# breezeduino.net
KiCad netlist of a schematic drawn in EAGLE
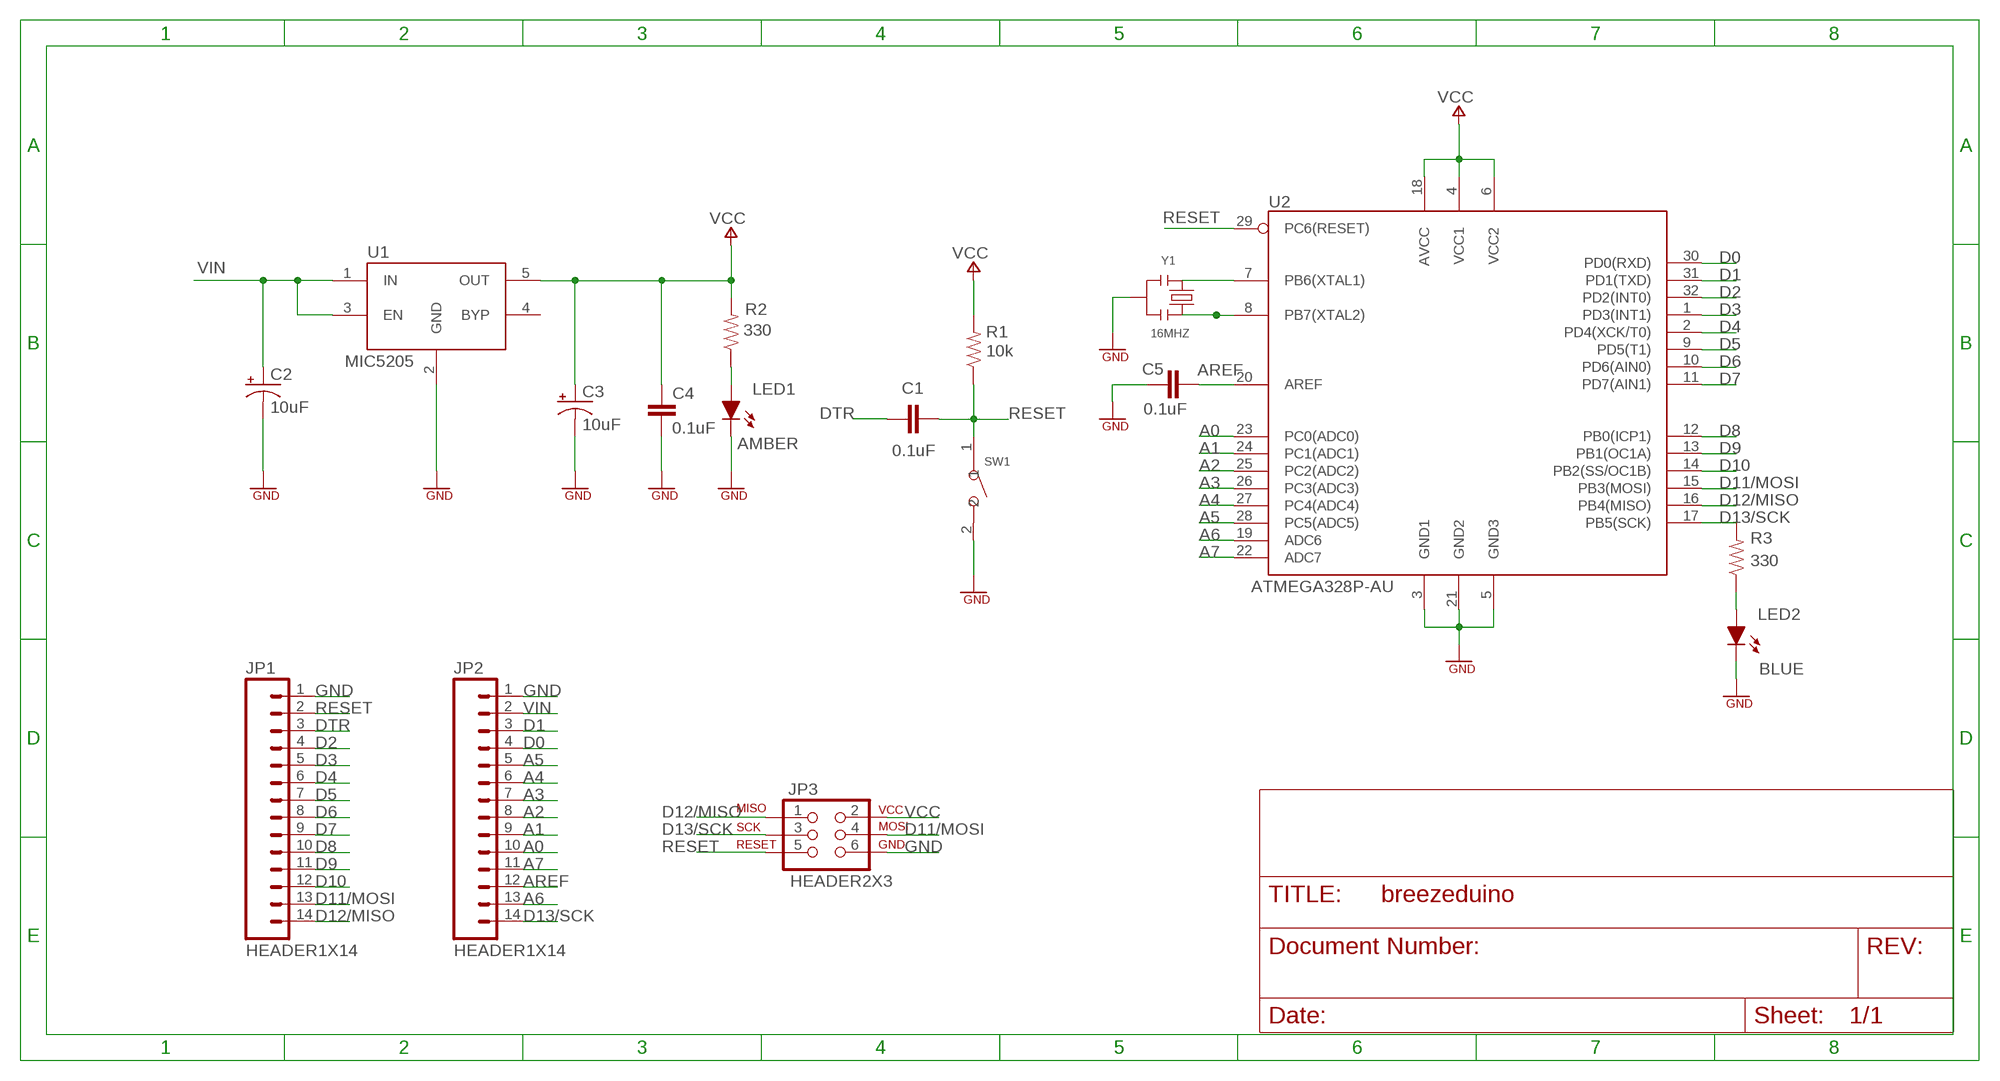
[diagram p0: schematic, sheet 1]

(export (version "E")
  (design (tool "Eeschema 10.0.6"))
  (components
    (comp (ref "C1")
      (value "0.1uF")
      (footprint "eagle-import:SMD0603")
      (libsource (lib "eagle-import") (part "CAP_0603"))
    )
    (comp (ref "C2")
      (value "10uF")
      (footprint "eagle-import:EIA3216")
      (libsource (lib "eagle-import") (part "CAP_TANT"))
    )
    (comp (ref "C3")
      (value "10uF")
      (footprint "eagle-import:EIA3216")
      (libsource (lib "eagle-import") (part "CAP_TANT"))
    )
    (comp (ref "C4")
      (value "0.1uF")
      (footprint "eagle-import:SMD0603")
      (libsource (lib "eagle-import") (part "CAP_0603"))
    )
    (comp (ref "C5")
      (value "0.1uF")
      (footprint "eagle-import:SMD0603")
      (libsource (lib "eagle-import") (part "CAP_0603"))
    )
    (comp (ref "JP1")
      (value "HEADER1X14")
      (footprint "eagle-import:1X14")
      (libsource (lib "eagle-import") (part "HEADER1X14"))
    )
    (comp (ref "JP2")
      (value "HEADER1X14")
      (footprint "eagle-import:1X14")
      (libsource (lib "eagle-import") (part "HEADER1X14"))
    )
    (comp (ref "JP3")
      (value "HEADER2X3")
      (footprint "eagle-import:2X3")
      (libsource (lib "eagle-import") (part "HEADER2X3"))
    )
    (comp (ref "LED1")
      (value "AMBER")
      (footprint "eagle-import:LED_0603")
      (libsource (lib "eagle-import") (part "LED_0603"))
    )
    (comp (ref "LED2")
      (value "BLUE")
      (footprint "eagle-import:LED_0805")
      (libsource (lib "eagle-import") (part "LED_0805"))
    )
    (comp (ref "R1")
      (value "10k")
      (footprint "eagle-import:SMD0603")
      (libsource (lib "eagle-import") (part "RES_0603"))
    )
    (comp (ref "R2")
      (value "330")
      (footprint "eagle-import:SMD0603")
      (libsource (lib "eagle-import") (part "RES_0603"))
    )
    (comp (ref "R3")
      (value "330")
      (footprint "eagle-import:SMD0603")
      (libsource (lib "eagle-import") (part "RES_0603"))
    )
    (comp (ref "SW1")
      (value "SMD-BUTTON(2P-3.0X2.5X1.2+0.4MM)-B3U-1000P-2P-SMD")
      (footprint "eagle-import:SW2-2.6-3.0X2.5X1.2+0.4MM")
      (fields (field (name "MPN") "B3U-1000P-2P-SMD"))
      (libsource (lib "eagle-import") (part "SMD-BUTTON(2P-3.0X2.5X1.2+0.4MM)-B3U-1000P-2P-SMD"))
    )
    (comp (ref "U1")
      (value "MIC5205")
      (footprint "eagle-import:SOT23-5")
      (libsource (lib "eagle-import") (part "MIC5205"))
    )
    (comp (ref "U2")
      (value "ATMEGA328P-AU")
      (footprint "eagle-import:TQFP32")
      (libsource (lib "eagle-import") (part "ATMEGA328P-AU"))
    )
    (comp (ref "Y1")
      (value "16MHZ")
      (footprint "eagle-import:X3-SMD-3.6X1.3X0.8MM")
      (fields (field (name "MPN") "CSTCE16M0V53-R0"))
      (libsource (lib "eagle-import") (part "SMD-RESONATOR-16MHZ-15PF-0.5%-40R(3P-3.2X1.3MM)"))
    )
  )
  (nets
    (net (code "1") (name "/A0") (class "Default")
      (node (ref "JP2") (pin "10") (pinfunction "10_10") (pintype "passive"))
      (node (ref "U2") (pin "23") (pinfunction "PC0(ADC0)_23") (pintype "bidirectional"))
    )
    (net (code "2") (name "/A1") (class "Default")
      (node (ref "JP2") (pin "9") (pinfunction "9_9") (pintype "passive"))
      (node (ref "U2") (pin "24") (pinfunction "PC1(ADC1)_24") (pintype "bidirectional"))
    )
    (net (code "3") (name "/A2") (class "Default")
      (node (ref "JP2") (pin "8") (pinfunction "8_8") (pintype "passive"))
      (node (ref "U2") (pin "25") (pinfunction "PC2(ADC2)_25") (pintype "bidirectional"))
    )
    (net (code "4") (name "/A3") (class "Default")
      (node (ref "JP2") (pin "7") (pinfunction "7_7") (pintype "passive"))
      (node (ref "U2") (pin "26") (pinfunction "PC3(ADC3)_26") (pintype "bidirectional"))
    )
    (net (code "5") (name "/A4") (class "Default")
      (node (ref "JP2") (pin "6") (pinfunction "6_6") (pintype "passive"))
      (node (ref "U2") (pin "27") (pinfunction "PC4(ADC4)_27") (pintype "bidirectional"))
    )
    (net (code "6") (name "/A5") (class "Default")
      (node (ref "JP2") (pin "5") (pinfunction "5_5") (pintype "passive"))
      (node (ref "U2") (pin "28") (pinfunction "PC5(ADC5)_28") (pintype "bidirectional"))
    )
    (net (code "7") (name "/A6") (class "Default")
      (node (ref "JP2") (pin "13") (pinfunction "13_13") (pintype "passive"))
      (node (ref "U2") (pin "19") (pinfunction "ADC6_19") (pintype "bidirectional"))
    )
    (net (code "8") (name "/A7") (class "Default")
      (node (ref "JP2") (pin "11") (pinfunction "11_11") (pintype "passive"))
      (node (ref "U2") (pin "22") (pinfunction "ADC7_22") (pintype "bidirectional"))
    )
    (net (code "9") (name "/AREF") (class "Default")
      (node (ref "C5") (pin "1") (pinfunction "1_1") (pintype "passive"))
      (node (ref "JP2") (pin "12") (pinfunction "12_12") (pintype "passive"))
      (node (ref "U2") (pin "20") (pinfunction "AREF_20") (pintype "bidirectional"))
    )
    (net (code "10") (name "/D0") (class "Default")
      (node (ref "JP2") (pin "4") (pinfunction "4_4") (pintype "passive"))
      (node (ref "U2") (pin "30") (pinfunction "PD0(RXD)_30") (pintype "bidirectional"))
    )
    (net (code "11") (name "/D1") (class "Default")
      (node (ref "JP2") (pin "3") (pinfunction "3_3") (pintype "passive"))
      (node (ref "U2") (pin "31") (pinfunction "PD1(TXD)_31") (pintype "bidirectional"))
    )
    (net (code "12") (name "/D2") (class "Default")
      (node (ref "JP1") (pin "4") (pinfunction "4_4") (pintype "passive"))
      (node (ref "U2") (pin "32") (pinfunction "PD2(INT0)_32") (pintype "bidirectional"))
    )
    (net (code "13") (name "/D3") (class "Default")
      (node (ref "JP1") (pin "5") (pinfunction "5_5") (pintype "passive"))
      (node (ref "U2") (pin "1") (pinfunction "PD3(INT1)_1") (pintype "bidirectional"))
    )
    (net (code "14") (name "/D4") (class "Default")
      (node (ref "JP1") (pin "6") (pinfunction "6_6") (pintype "passive"))
      (node (ref "U2") (pin "2") (pinfunction "PD4(XCK/T0)_2") (pintype "bidirectional"))
    )
    (net (code "15") (name "/D5") (class "Default")
      (node (ref "JP1") (pin "7") (pinfunction "7_7") (pintype "passive"))
      (node (ref "U2") (pin "9") (pinfunction "PD5(T1)_9") (pintype "bidirectional"))
    )
    (net (code "16") (name "/D6") (class "Default")
      (node (ref "JP1") (pin "8") (pinfunction "8_8") (pintype "passive"))
      (node (ref "U2") (pin "10") (pinfunction "PD6(AIN0)_10") (pintype "bidirectional"))
    )
    (net (code "17") (name "/D7") (class "Default")
      (node (ref "JP1") (pin "9") (pinfunction "9_9") (pintype "passive"))
      (node (ref "U2") (pin "11") (pinfunction "PD7(AIN1)_11") (pintype "bidirectional"))
    )
    (net (code "18") (name "/D8") (class "Default")
      (node (ref "JP1") (pin "10") (pinfunction "10_10") (pintype "passive"))
      (node (ref "U2") (pin "12") (pinfunction "PB0(ICP1)_12") (pintype "bidirectional"))
    )
    (net (code "19") (name "/D9") (class "Default")
      (node (ref "JP1") (pin "11") (pinfunction "11_11") (pintype "passive"))
      (node (ref "U2") (pin "13") (pinfunction "PB1(OC1A)_13") (pintype "bidirectional"))
    )
    (net (code "20") (name "/D10") (class "Default")
      (node (ref "JP1") (pin "12") (pinfunction "12_12") (pintype "passive"))
      (node (ref "U2") (pin "14") (pinfunction "PB2(SS/OC1B)_14") (pintype "bidirectional"))
    )
    (net (code "21") (name "/D11{slash}MOSI") (class "Default")
      (node (ref "JP1") (pin "13") (pinfunction "13_13") (pintype "passive"))
      (node (ref "JP3") (pin "4") (pinfunction "4_4") (pintype "passive"))
      (node (ref "U2") (pin "15") (pinfunction "PB3(MOSI)_15") (pintype "bidirectional"))
    )
    (net (code "22") (name "/D12{slash}MISO") (class "Default")
      (node (ref "JP1") (pin "14") (pinfunction "14_14") (pintype "passive"))
      (node (ref "JP3") (pin "1") (pinfunction "1_1") (pintype "passive"))
      (node (ref "U2") (pin "16") (pinfunction "PB4(MISO)_16") (pintype "bidirectional"))
    )
    (net (code "23") (name "/D13{slash}SCK") (class "Default")
      (node (ref "JP2") (pin "14") (pinfunction "14_14") (pintype "passive"))
      (node (ref "JP3") (pin "3") (pinfunction "3_3") (pintype "passive"))
      (node (ref "R3") (pin "2") (pinfunction "2_2") (pintype "passive"))
      (node (ref "U2") (pin "17") (pinfunction "PB5(SCK)_17") (pintype "bidirectional"))
    )
    (net (code "24") (name "/DTR") (class "Default")
      (node (ref "C1") (pin "1") (pinfunction "1_1") (pintype "passive"))
      (node (ref "JP1") (pin "3") (pinfunction "3_3") (pintype "passive"))
    )
    (net (code "25") (name "/RESET") (class "Default")
      (node (ref "C1") (pin "2") (pinfunction "2_2") (pintype "passive"))
      (node (ref "JP1") (pin "2") (pinfunction "2_2") (pintype "passive"))
      (node (ref "JP3") (pin "5") (pinfunction "5_5") (pintype "passive"))
      (node (ref "R1") (pin "1") (pinfunction "1_1") (pintype "passive"))
      (node (ref "SW1") (pin "1") (pinfunction "1_1") (pintype "bidirectional"))
      (node (ref "U2") (pin "29") (pinfunction "PC6(RESET)_29") (pintype "bidirectional"))
    )
    (net (code "26") (name "/VIN") (class "Default")
      (node (ref "C2") (pin "A") (pinfunction "+_A") (pintype "passive"))
      (node (ref "JP2") (pin "2") (pinfunction "2_2") (pintype "passive"))
      (node (ref "U1") (pin "1") (pinfunction "IN_1") (pintype "bidirectional"))
      (node (ref "U1") (pin "3") (pinfunction "EN_3") (pintype "bidirectional"))
    )
    (net (code "27") (name "GND") (class "Default")
      (node (ref "C2") (pin "C") (pinfunction "-_C") (pintype "passive"))
      (node (ref "C3") (pin "C") (pinfunction "-_C") (pintype "passive"))
      (node (ref "C4") (pin "2") (pinfunction "2_2") (pintype "passive"))
      (node (ref "C5") (pin "2") (pinfunction "2_2") (pintype "passive"))
      (node (ref "JP1") (pin "1") (pinfunction "1_1") (pintype "passive"))
      (node (ref "JP2") (pin "1") (pinfunction "1_1") (pintype "passive"))
      (node (ref "JP3") (pin "6") (pinfunction "6_6") (pintype "passive"))
      (node (ref "LED1") (pin "C") (pinfunction "C_C") (pintype "passive"))
      (node (ref "LED2") (pin "C") (pinfunction "C_C") (pintype "passive"))
      (node (ref "SW1") (pin "2") (pinfunction "2_2") (pintype "bidirectional"))
      (node (ref "U1") (pin "2") (pinfunction "GND_2") (pintype "bidirectional"))
      (node (ref "U2") (pin "21") (pinfunction "GND2_21") (pintype "bidirectional"))
      (node (ref "U2") (pin "3") (pinfunction "GND1_3") (pintype "bidirectional"))
      (node (ref "U2") (pin "5") (pinfunction "GND3_5") (pintype "bidirectional"))
      (node (ref "Y1") (pin "2") (pinfunction "2_2") (pintype "passive"))
    )
    (net (code "28") (name "Net-(LED1-PadA)") (class "Default")
      (node (ref "LED1") (pin "A") (pinfunction "A_A") (pintype "passive"))
      (node (ref "R2") (pin "1") (pinfunction "1_1") (pintype "passive"))
    )
    (net (code "29") (name "Net-(LED2-PadA)") (class "Default")
      (node (ref "LED2") (pin "A") (pinfunction "A_A") (pintype "passive"))
      (node (ref "R3") (pin "1") (pinfunction "1_1") (pintype "passive"))
    )
    (net (code "30") (name "Net-(U2-PB6(XTAL1))") (class "Default")
      (node (ref "U2") (pin "7") (pinfunction "PB6(XTAL1)_7") (pintype "bidirectional"))
      (node (ref "Y1") (pin "1") (pinfunction "1_1") (pintype "passive"))
    )
    (net (code "31") (name "Net-(U2-PB7(XTAL2))") (class "Default")
      (node (ref "U2") (pin "8") (pinfunction "PB7(XTAL2)_8") (pintype "bidirectional"))
      (node (ref "Y1") (pin "3") (pinfunction "3_3") (pintype "passive"))
    )
    (net (code "32") (name "VCC") (class "Default")
      (node (ref "C3") (pin "A") (pinfunction "+_A") (pintype "passive"))
      (node (ref "C4") (pin "1") (pinfunction "1_1") (pintype "passive"))
      (node (ref "JP3") (pin "2") (pinfunction "2_2") (pintype "passive"))
      (node (ref "R1") (pin "2") (pinfunction "2_2") (pintype "passive"))
      (node (ref "R2") (pin "2") (pinfunction "2_2") (pintype "passive"))
      (node (ref "U1") (pin "5") (pinfunction "OUT_5") (pintype "bidirectional"))
      (node (ref "U2") (pin "18") (pinfunction "AVCC_18") (pintype "bidirectional"))
      (node (ref "U2") (pin "4") (pinfunction "VCC1_4") (pintype "bidirectional"))
      (node (ref "U2") (pin "6") (pinfunction "VCC2_6") (pintype "bidirectional"))
    )
    (net (code "33") (name "unconnected-(U1-BYP-Pad4)") (class "Default")
      (node (ref "U1") (pin "4") (pinfunction "BYP_4") (pintype "passive"))
    )
  )
)
